# esp32-weatherstation-v1.net
KiCad netlist of a schematic drawn in EAGLE
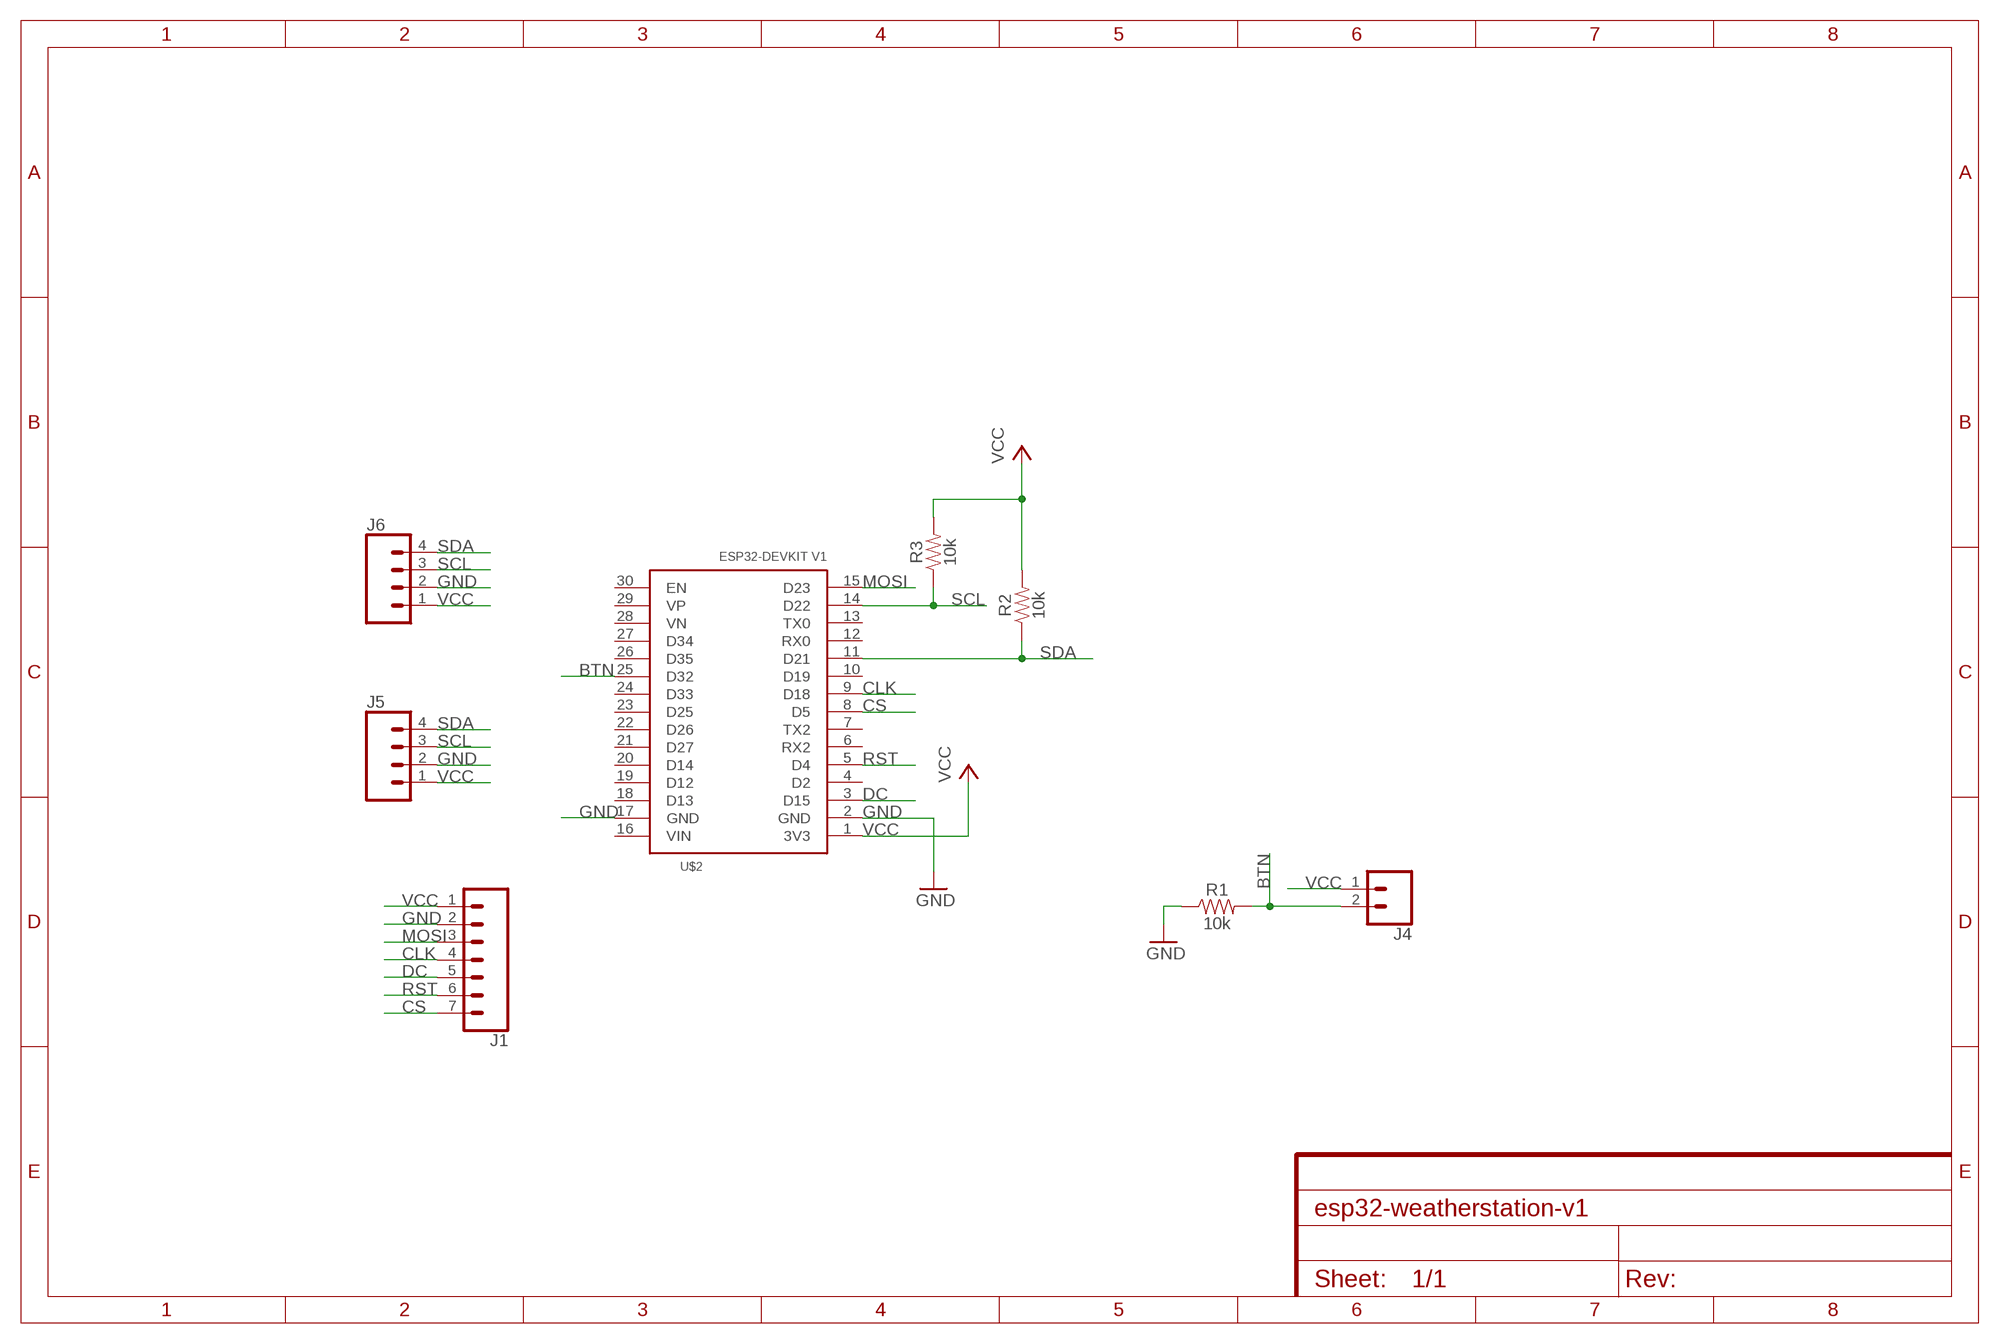
[diagram p0: schematic, sheet 1]

(export (version "E")
  (design (tool "Eeschema 10.0.6"))
  (components
    (comp (ref "J1")
      (value "CONN_07")
      (footprint "eagle-import:1X07")
      (libsource (lib "eagle-import") (part "CONN_07"))
    )
    (comp (ref "J4")
      (value "CONN_02")
      (footprint "eagle-import:1X02")
      (libsource (lib "eagle-import") (part "CONN_02"))
    )
    (comp (ref "J5")
      (value "CONN_04POLAR")
      (footprint "eagle-import:MOLEX-1X4")
      (libsource (lib "eagle-import") (part "CONN_04POLAR"))
    )
    (comp (ref "J6")
      (value "CONN_04POLAR")
      (footprint "eagle-import:MOLEX-1X4")
      (libsource (lib "eagle-import") (part "CONN_04POLAR"))
    )
    (comp (ref "R1")
      (value "10k")
      (footprint "eagle-import:AXIAL-0.3")
      (libsource (lib "eagle-import") (part "10KOHM-HORIZ-1/4W-1%"))
    )
    (comp (ref "R2")
      (value "10k")
      (footprint "eagle-import:AXIAL-0.3")
      (libsource (lib "eagle-import") (part "10KOHM-HORIZ-1/4W-1%"))
    )
    (comp (ref "R3")
      (value "10k")
      (footprint "eagle-import:AXIAL-0.3")
      (libsource (lib "eagle-import") (part "10KOHM-HORIZ-1/4W-1%"))
    )
    (comp (ref "U$2")
      (value "DOIT-ESP32DEVKIT1")
      (footprint "eagle-import:ESP32-DEVKITV1")
      (libsource (lib "eagle-import") (part "DOIT-ESP32DEVKIT1"))
    )
  )
  (nets
    (net (code "1") (name "/BTN") (class "Default")
      (node (ref "J4") (pin "2") (pinfunction "2_2") (pintype "passive"))
      (node (ref "R1") (pin "P$2") (pinfunction "2_P$2") (pintype "passive"))
      (node (ref "U$2") (pin "25") (pinfunction "D32_25") (pintype "bidirectional"))
    )
    (net (code "2") (name "/CLK") (class "Default")
      (node (ref "J1") (pin "4") (pinfunction "4_4") (pintype "passive"))
      (node (ref "U$2") (pin "9") (pinfunction "D18_9") (pintype "bidirectional"))
    )
    (net (code "3") (name "/CS") (class "Default")
      (node (ref "J1") (pin "7") (pinfunction "7_7") (pintype "passive"))
      (node (ref "U$2") (pin "8") (pinfunction "D5_8") (pintype "bidirectional"))
    )
    (net (code "4") (name "/DC") (class "Default")
      (node (ref "J1") (pin "5") (pinfunction "5_5") (pintype "passive"))
      (node (ref "U$2") (pin "3") (pinfunction "D15_3") (pintype "bidirectional"))
    )
    (net (code "5") (name "/MOSI") (class "Default")
      (node (ref "J1") (pin "3") (pinfunction "3_3") (pintype "passive"))
      (node (ref "U$2") (pin "15") (pinfunction "D23_15") (pintype "bidirectional"))
    )
    (net (code "6") (name "/RST") (class "Default")
      (node (ref "J1") (pin "6") (pinfunction "6_6") (pintype "passive"))
      (node (ref "U$2") (pin "5") (pinfunction "D4_5") (pintype "bidirectional"))
    )
    (net (code "7") (name "/SCL") (class "Default")
      (node (ref "J5") (pin "3") (pinfunction "3_3") (pintype "passive"))
      (node (ref "J6") (pin "3") (pinfunction "3_3") (pintype "passive"))
      (node (ref "R3") (pin "P$1") (pinfunction "1_P$1") (pintype "passive"))
      (node (ref "U$2") (pin "14") (pinfunction "D22_14") (pintype "bidirectional"))
    )
    (net (code "8") (name "/SDA") (class "Default")
      (node (ref "J5") (pin "4") (pinfunction "4_4") (pintype "passive"))
      (node (ref "J6") (pin "4") (pinfunction "4_4") (pintype "passive"))
      (node (ref "R2") (pin "P$1") (pinfunction "1_P$1") (pintype "passive"))
      (node (ref "U$2") (pin "11") (pinfunction "D21_11") (pintype "bidirectional"))
    )
    (net (code "9") (name "GND") (class "Default")
      (node (ref "J1") (pin "2") (pinfunction "2_2") (pintype "passive"))
      (node (ref "J5") (pin "2") (pinfunction "2_2") (pintype "passive"))
      (node (ref "J6") (pin "2") (pinfunction "2_2") (pintype "passive"))
      (node (ref "R1") (pin "P$1") (pinfunction "1_P$1") (pintype "passive"))
      (node (ref "U$2") (pin "17") (pinfunction "GND_17") (pintype "bidirectional"))
      (node (ref "U$2") (pin "2") (pinfunction "GND_2") (pintype "bidirectional"))
    )
    (net (code "10") (name "VCC") (class "Default")
      (node (ref "J1") (pin "1") (pinfunction "1_1") (pintype "passive"))
      (node (ref "J4") (pin "1") (pinfunction "1_1") (pintype "passive"))
      (node (ref "J5") (pin "1") (pinfunction "1_1") (pintype "passive"))
      (node (ref "J6") (pin "1") (pinfunction "1_1") (pintype "passive"))
      (node (ref "R2") (pin "P$2") (pinfunction "2_P$2") (pintype "passive"))
      (node (ref "R3") (pin "P$2") (pinfunction "2_P$2") (pintype "passive"))
      (node (ref "U$2") (pin "1") (pinfunction "3V3_1") (pintype "bidirectional"))
    )
    (net (code "11") (name "unconnected-(U$2-D2-Pad4)") (class "Default")
      (node (ref "U$2") (pin "4") (pinfunction "D2_4") (pintype "bidirectional"))
    )
    (net (code "12") (name "unconnected-(U$2-D12-Pad19)") (class "Default")
      (node (ref "U$2") (pin "19") (pinfunction "D12_19") (pintype "bidirectional"))
    )
    (net (code "13") (name "unconnected-(U$2-D13-Pad18)") (class "Default")
      (node (ref "U$2") (pin "18") (pinfunction "D13_18") (pintype "bidirectional"))
    )
    (net (code "14") (name "unconnected-(U$2-D14-Pad20)") (class "Default")
      (node (ref "U$2") (pin "20") (pinfunction "D14_20") (pintype "bidirectional"))
    )
    (net (code "15") (name "unconnected-(U$2-D19-Pad10)") (class "Default")
      (node (ref "U$2") (pin "10") (pinfunction "D19_10") (pintype "bidirectional"))
    )
    (net (code "16") (name "unconnected-(U$2-D25-Pad23)") (class "Default")
      (node (ref "U$2") (pin "23") (pinfunction "D25_23") (pintype "bidirectional"))
    )
    (net (code "17") (name "unconnected-(U$2-D26-Pad22)") (class "Default")
      (node (ref "U$2") (pin "22") (pinfunction "D26_22") (pintype "bidirectional"))
    )
    (net (code "18") (name "unconnected-(U$2-D27-Pad21)") (class "Default")
      (node (ref "U$2") (pin "21") (pinfunction "D27_21") (pintype "bidirectional"))
    )
    (net (code "19") (name "unconnected-(U$2-D33-Pad24)") (class "Default")
      (node (ref "U$2") (pin "24") (pinfunction "D33_24") (pintype "bidirectional"))
    )
    (net (code "20") (name "unconnected-(U$2-D34-Pad27)") (class "Default")
      (node (ref "U$2") (pin "27") (pinfunction "D34_27") (pintype "bidirectional"))
    )
    (net (code "21") (name "unconnected-(U$2-D35-Pad26)") (class "Default")
      (node (ref "U$2") (pin "26") (pinfunction "D35_26") (pintype "bidirectional"))
    )
    (net (code "22") (name "unconnected-(U$2-EN-Pad30)") (class "Default")
      (node (ref "U$2") (pin "30") (pinfunction "EN_30") (pintype "bidirectional"))
    )
    (net (code "23") (name "unconnected-(U$2-RX0-Pad12)") (class "Default")
      (node (ref "U$2") (pin "12") (pinfunction "RX0_12") (pintype "bidirectional"))
    )
    (net (code "24") (name "unconnected-(U$2-RX2-Pad6)") (class "Default")
      (node (ref "U$2") (pin "6") (pinfunction "RX2_6") (pintype "bidirectional"))
    )
    (net (code "25") (name "unconnected-(U$2-TX0-Pad13)") (class "Default")
      (node (ref "U$2") (pin "13") (pinfunction "TX0_13") (pintype "bidirectional"))
    )
    (net (code "26") (name "unconnected-(U$2-TX2-Pad7)") (class "Default")
      (node (ref "U$2") (pin "7") (pinfunction "TX2_7") (pintype "bidirectional"))
    )
    (net (code "27") (name "unconnected-(U$2-VIN-Pad16)") (class "Default")
      (node (ref "U$2") (pin "16") (pinfunction "VIN_16") (pintype "bidirectional"))
    )
    (net (code "28") (name "unconnected-(U$2-VN-Pad28)") (class "Default")
      (node (ref "U$2") (pin "28") (pinfunction "VN_28") (pintype "bidirectional"))
    )
    (net (code "29") (name "unconnected-(U$2-VP-Pad29)") (class "Default")
      (node (ref "U$2") (pin "29") (pinfunction "VP_29") (pintype "bidirectional"))
    )
  )
)
